# TA_v2.net
KiCad netlist of a schematic drawn in EAGLE
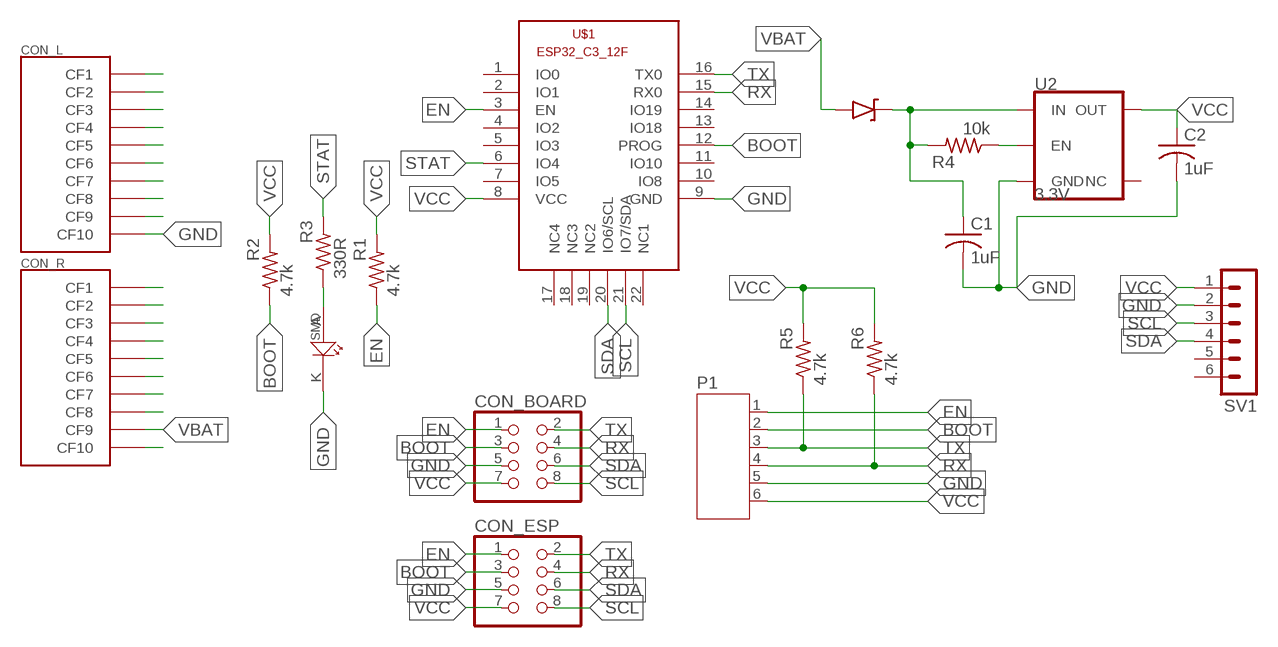
[diagram p0: schematic, sheet 1]

(export (version "E")
  (design (tool "Eeschema 10.0.6"))
  (components
    (comp (ref "C1")
      (value "1uF")
      (footprint "eagle-import:C0805")
      (libsource (lib "eagle-import") (part "C-USC0805"))
    )
    (comp (ref "C2")
      (value "1uF")
      (footprint "eagle-import:C0805")
      (libsource (lib "eagle-import") (part "C-USC0805"))
    )
    (comp (ref "CON_BOARD")
      (value "PINHD-2X4")
      (footprint "eagle-import:2X04")
      (libsource (lib "eagle-import") (part "PINHD-2X4"))
    )
    (comp (ref "CON_ESP")
      (value "PINHD-2X4")
      (footprint "eagle-import:2X04")
      (libsource (lib "eagle-import") (part "PINHD-2X4"))
    )
    (comp (ref "CON_L")
      (value "FEMALE_CON")
      (footprint "eagle-import:FEMALE_HEADER_2")
      (libsource (lib "eagle-import") (part "FEMALE_CON"))
    )
    (comp (ref "CON_R")
      (value "FEMALE_CON")
      (footprint "eagle-import:FEMALE_HEADER_2")
      (libsource (lib "eagle-import") (part "FEMALE_CON"))
    )
    (comp (ref "P1")
      (value "JST-PH6")
      (footprint "eagle-import:JST-PH6")
      (libsource (lib "eagle-import") (part "JST-PH6"))
    )
    (comp (ref "R1")
      (value "4.7k")
      (footprint "eagle-import:R0603")
      (libsource (lib "eagle-import") (part "R-US_R0603"))
    )
    (comp (ref "R2")
      (value "4.7k")
      (footprint "eagle-import:R0603")
      (libsource (lib "eagle-import") (part "R-US_R0603"))
    )
    (comp (ref "R3")
      (value "330R")
      (footprint "eagle-import:R0603")
      (libsource (lib "eagle-import") (part "R-US_R0603"))
    )
    (comp (ref "R4")
      (value "10k")
      (footprint "eagle-import:R0603")
      (libsource (lib "eagle-import") (part "R-US_R0603"))
    )
    (comp (ref "R5")
      (value "4.7k")
      (footprint "eagle-import:R0603")
      (libsource (lib "eagle-import") (part "R-US_R0603"))
    )
    (comp (ref "R6")
      (value "4.7k")
      (footprint "eagle-import:R0603")
      (libsource (lib "eagle-import") (part "R-US_R0603"))
    )
    (comp (ref "SV1")
      (value "MA06-1")
      (footprint "eagle-import:MA06-1")
      (libsource (lib "eagle-import") (part "MA06-1"))
    )
    (comp (ref "U$1")
      (value "ESP32-C3-12FESP32-C3-12F")
      (footprint "eagle-import:ESP32-C3-12F")
      (libsource (lib "eagle-import") (part "ESP32-C3-12FESP32-C3-12F"))
    )
    (comp (ref "U$2")
      (value "1N5819")
      (footprint "eagle-import:SOT-323")
      (libsource (lib "eagle-import") (part "1N5819"))
    )
    (comp (ref "U$3")
      (value "LED_SMD")
      (footprint "eagle-import:LED_0603")
      (libsource (lib "eagle-import") (part "LED_SMD"))
    )
    (comp (ref "U2")
      (value "3.3V")
      (footprint "eagle-import:SOT23-5")
      (libsource (lib "eagle-import") (part "V_REG_AP2112K-3.3V"))
    )
  )
  (nets
    (net (code "1") (name "BOOT") (class "Default")
      (node (ref "CON_BOARD") (pin "3") (pinfunction "3_3") (pintype "passive"))
      (node (ref "CON_ESP") (pin "3") (pinfunction "3_3") (pintype "passive"))
      (node (ref "P1") (pin "2") (pinfunction "2_2") (pintype "passive"))
      (node (ref "R2") (pin "1") (pinfunction "1_1") (pintype "passive"))
      (node (ref "U$1") (pin "12") (pinfunction "PROG_12") (pintype "bidirectional"))
    )
    (net (code "2") (name "EN") (class "Default")
      (node (ref "CON_BOARD") (pin "1") (pinfunction "1_1") (pintype "passive"))
      (node (ref "CON_ESP") (pin "1") (pinfunction "1_1") (pintype "passive"))
      (node (ref "P1") (pin "1") (pinfunction "1_1") (pintype "passive"))
      (node (ref "R1") (pin "1") (pinfunction "1_1") (pintype "passive"))
      (node (ref "U$1") (pin "3") (pinfunction "EN_3") (pintype "bidirectional"))
    )
    (net (code "3") (name "GND") (class "Default")
      (node (ref "C1") (pin "2") (pinfunction "2_2") (pintype "passive"))
      (node (ref "C2") (pin "2") (pinfunction "2_2") (pintype "passive"))
      (node (ref "CON_BOARD") (pin "5") (pinfunction "5_5") (pintype "passive"))
      (node (ref "CON_ESP") (pin "5") (pinfunction "5_5") (pintype "passive"))
      (node (ref "CON_L") (pin "CF10") (pinfunction "CF10_CF10") (pintype "bidirectional"))
      (node (ref "P1") (pin "5") (pinfunction "5_5") (pintype "passive"))
      (node (ref "SV1") (pin "2") (pinfunction "2_2") (pintype "passive"))
      (node (ref "U$1") (pin "9") (pinfunction "GND_9") (pintype "bidirectional"))
      (node (ref "U$3") (pin "K") (pinfunction "K_K") (pintype "bidirectional"))
      (node (ref "U2") (pin "2") (pinfunction "GND_2") (pintype "input"))
    )
    (net (code "4") (name "Net-(R3-Pad1)") (class "Default")
      (node (ref "R3") (pin "1") (pinfunction "1_1") (pintype "passive"))
      (node (ref "U$3") (pin "A") (pinfunction "A_A") (pintype "bidirectional"))
    )
    (net (code "5") (name "Net-(U2-EN)") (class "Default")
      (node (ref "R4") (pin "1") (pinfunction "1_1") (pintype "passive"))
      (node (ref "U2") (pin "3") (pinfunction "EN_3") (pintype "input"))
    )
    (net (code "6") (name "Net-(U2-IN)") (class "Default")
      (node (ref "C1") (pin "1") (pinfunction "1_1") (pintype "passive"))
      (node (ref "R4") (pin "2") (pinfunction "2_2") (pintype "passive"))
      (node (ref "U$2") (pin "K") (pinfunction "K_K") (pintype "bidirectional"))
      (node (ref "U2") (pin "1") (pinfunction "IN_1") (pintype "input"))
    )
    (net (code "7") (name "RX") (class "Default")
      (node (ref "CON_BOARD") (pin "4") (pinfunction "4_4") (pintype "passive"))
      (node (ref "CON_ESP") (pin "4") (pinfunction "4_4") (pintype "passive"))
      (node (ref "P1") (pin "4") (pinfunction "4_4") (pintype "passive"))
      (node (ref "R6") (pin "1") (pinfunction "1_1") (pintype "passive"))
      (node (ref "U$1") (pin "15") (pinfunction "RX0_15") (pintype "bidirectional"))
    )
    (net (code "8") (name "SCL") (class "Default")
      (node (ref "CON_BOARD") (pin "8") (pinfunction "8_8") (pintype "passive"))
      (node (ref "CON_ESP") (pin "8") (pinfunction "8_8") (pintype "passive"))
      (node (ref "SV1") (pin "3") (pinfunction "3_3") (pintype "passive"))
      (node (ref "U$1") (pin "21") (pinfunction "IO7/SDA_21") (pintype "bidirectional"))
    )
    (net (code "9") (name "SDA") (class "Default")
      (node (ref "CON_BOARD") (pin "6") (pinfunction "6_6") (pintype "passive"))
      (node (ref "CON_ESP") (pin "6") (pinfunction "6_6") (pintype "passive"))
      (node (ref "SV1") (pin "4") (pinfunction "4_4") (pintype "passive"))
      (node (ref "U$1") (pin "20") (pinfunction "IO6/SCL_20") (pintype "bidirectional"))
    )
    (net (code "10") (name "STAT") (class "Default")
      (node (ref "R3") (pin "2") (pinfunction "2_2") (pintype "passive"))
      (node (ref "U$1") (pin "6") (pinfunction "IO4_6") (pintype "bidirectional"))
    )
    (net (code "11") (name "TX") (class "Default")
      (node (ref "CON_BOARD") (pin "2") (pinfunction "2_2") (pintype "passive"))
      (node (ref "CON_ESP") (pin "2") (pinfunction "2_2") (pintype "passive"))
      (node (ref "P1") (pin "3") (pinfunction "3_3") (pintype "passive"))
      (node (ref "R5") (pin "1") (pinfunction "1_1") (pintype "passive"))
      (node (ref "U$1") (pin "16") (pinfunction "TX0_16") (pintype "bidirectional"))
    )
    (net (code "12") (name "VBAT") (class "Default")
      (node (ref "CON_R") (pin "CF9") (pinfunction "CF9_CF9") (pintype "bidirectional"))
      (node (ref "U$2") (pin "A") (pinfunction "A_A") (pintype "bidirectional"))
    )
    (net (code "13") (name "VCC") (class "Default")
      (node (ref "C2") (pin "1") (pinfunction "1_1") (pintype "passive"))
      (node (ref "CON_BOARD") (pin "7") (pinfunction "7_7") (pintype "passive"))
      (node (ref "CON_ESP") (pin "7") (pinfunction "7_7") (pintype "passive"))
      (node (ref "P1") (pin "6") (pinfunction "6_6") (pintype "passive"))
      (node (ref "R1") (pin "2") (pinfunction "2_2") (pintype "passive"))
      (node (ref "R2") (pin "2") (pinfunction "2_2") (pintype "passive"))
      (node (ref "R5") (pin "2") (pinfunction "2_2") (pintype "passive"))
      (node (ref "R6") (pin "2") (pinfunction "2_2") (pintype "passive"))
      (node (ref "SV1") (pin "1") (pinfunction "1_1") (pintype "passive"))
      (node (ref "U$1") (pin "8") (pinfunction "VCC_8") (pintype "bidirectional"))
      (node (ref "U2") (pin "5") (pinfunction "OUT_5") (pintype "passive"))
    )
    (net (code "14") (name "unconnected-(CON_L-PadCF1)") (class "Default")
      (node (ref "CON_L") (pin "CF1") (pinfunction "CF1_CF1") (pintype "bidirectional"))
    )
    (net (code "15") (name "unconnected-(CON_L-PadCF2)") (class "Default")
      (node (ref "CON_L") (pin "CF2") (pinfunction "CF2_CF2") (pintype "bidirectional"))
    )
    (net (code "16") (name "unconnected-(CON_L-PadCF3)") (class "Default")
      (node (ref "CON_L") (pin "CF3") (pinfunction "CF3_CF3") (pintype "bidirectional"))
    )
    (net (code "17") (name "unconnected-(CON_L-PadCF4)") (class "Default")
      (node (ref "CON_L") (pin "CF4") (pinfunction "CF4_CF4") (pintype "bidirectional"))
    )
    (net (code "18") (name "unconnected-(CON_L-PadCF5)") (class "Default")
      (node (ref "CON_L") (pin "CF5") (pinfunction "CF5_CF5") (pintype "bidirectional"))
    )
    (net (code "19") (name "unconnected-(CON_L-PadCF6)") (class "Default")
      (node (ref "CON_L") (pin "CF6") (pinfunction "CF6_CF6") (pintype "bidirectional"))
    )
    (net (code "20") (name "unconnected-(CON_L-PadCF7)") (class "Default")
      (node (ref "CON_L") (pin "CF7") (pinfunction "CF7_CF7") (pintype "bidirectional"))
    )
    (net (code "21") (name "unconnected-(CON_L-PadCF8)") (class "Default")
      (node (ref "CON_L") (pin "CF8") (pinfunction "CF8_CF8") (pintype "bidirectional"))
    )
    (net (code "22") (name "unconnected-(CON_L-PadCF9)") (class "Default")
      (node (ref "CON_L") (pin "CF9") (pinfunction "CF9_CF9") (pintype "bidirectional"))
    )
    (net (code "23") (name "unconnected-(CON_R-PadCF1)") (class "Default")
      (node (ref "CON_R") (pin "CF1") (pinfunction "CF1_CF1") (pintype "bidirectional"))
    )
    (net (code "24") (name "unconnected-(CON_R-PadCF2)") (class "Default")
      (node (ref "CON_R") (pin "CF2") (pinfunction "CF2_CF2") (pintype "bidirectional"))
    )
    (net (code "25") (name "unconnected-(CON_R-PadCF3)") (class "Default")
      (node (ref "CON_R") (pin "CF3") (pinfunction "CF3_CF3") (pintype "bidirectional"))
    )
    (net (code "26") (name "unconnected-(CON_R-PadCF4)") (class "Default")
      (node (ref "CON_R") (pin "CF4") (pinfunction "CF4_CF4") (pintype "bidirectional"))
    )
    (net (code "27") (name "unconnected-(CON_R-PadCF5)") (class "Default")
      (node (ref "CON_R") (pin "CF5") (pinfunction "CF5_CF5") (pintype "bidirectional"))
    )
    (net (code "28") (name "unconnected-(CON_R-PadCF6)") (class "Default")
      (node (ref "CON_R") (pin "CF6") (pinfunction "CF6_CF6") (pintype "bidirectional"))
    )
    (net (code "29") (name "unconnected-(CON_R-PadCF7)") (class "Default")
      (node (ref "CON_R") (pin "CF7") (pinfunction "CF7_CF7") (pintype "bidirectional"))
    )
    (net (code "30") (name "unconnected-(CON_R-PadCF8)") (class "Default")
      (node (ref "CON_R") (pin "CF8") (pinfunction "CF8_CF8") (pintype "bidirectional"))
    )
    (net (code "31") (name "unconnected-(CON_R-PadCF10)") (class "Default")
      (node (ref "CON_R") (pin "CF10") (pinfunction "CF10_CF10") (pintype "bidirectional"))
    )
    (net (code "32") (name "unconnected-(SV1-Pad5)") (class "Default")
      (node (ref "SV1") (pin "5") (pinfunction "5_5") (pintype "passive"))
    )
    (net (code "33") (name "unconnected-(SV1-Pad6)") (class "Default")
      (node (ref "SV1") (pin "6") (pinfunction "6_6") (pintype "passive"))
    )
    (net (code "34") (name "unconnected-(U$1-IO0-Pad1)") (class "Default")
      (node (ref "U$1") (pin "1") (pinfunction "IO0_1") (pintype "bidirectional"))
    )
    (net (code "35") (name "unconnected-(U$1-IO1-Pad2)") (class "Default")
      (node (ref "U$1") (pin "2") (pinfunction "IO1_2") (pintype "bidirectional"))
    )
    (net (code "36") (name "unconnected-(U$1-IO2-Pad4)") (class "Default")
      (node (ref "U$1") (pin "4") (pinfunction "IO2_4") (pintype "bidirectional"))
    )
    (net (code "37") (name "unconnected-(U$1-IO3-Pad5)") (class "Default")
      (node (ref "U$1") (pin "5") (pinfunction "IO3_5") (pintype "bidirectional"))
    )
    (net (code "38") (name "unconnected-(U$1-IO5-Pad7)") (class "Default")
      (node (ref "U$1") (pin "7") (pinfunction "IO5_7") (pintype "bidirectional"))
    )
    (net (code "39") (name "unconnected-(U$1-IO8-Pad10)") (class "Default")
      (node (ref "U$1") (pin "10") (pinfunction "IO8_10") (pintype "bidirectional"))
    )
    (net (code "40") (name "unconnected-(U$1-IO10-Pad11)") (class "Default")
      (node (ref "U$1") (pin "11") (pinfunction "IO10_11") (pintype "bidirectional"))
    )
    (net (code "41") (name "unconnected-(U$1-IO18-Pad13)") (class "Default")
      (node (ref "U$1") (pin "13") (pinfunction "IO18_13") (pintype "bidirectional"))
    )
    (net (code "42") (name "unconnected-(U$1-IO19-Pad14)") (class "Default")
      (node (ref "U$1") (pin "14") (pinfunction "IO19_14") (pintype "bidirectional"))
    )
    (net (code "43") (name "unconnected-(U$1-NC1-Pad22)") (class "Default")
      (node (ref "U$1") (pin "22") (pinfunction "NC1_22") (pintype "bidirectional"))
    )
    (net (code "44") (name "unconnected-(U$1-NC2-Pad19)") (class "Default")
      (node (ref "U$1") (pin "19") (pinfunction "NC2_19") (pintype "bidirectional"))
    )
    (net (code "45") (name "unconnected-(U$1-NC3-Pad18)") (class "Default")
      (node (ref "U$1") (pin "18") (pinfunction "NC3_18") (pintype "bidirectional"))
    )
    (net (code "46") (name "unconnected-(U$1-NC4-Pad17)") (class "Default")
      (node (ref "U$1") (pin "17") (pinfunction "NC4_17") (pintype "bidirectional"))
    )
    (net (code "47") (name "unconnected-(U2-NC-Pad4)") (class "Default")
      (node (ref "U2") (pin "4") (pinfunction "NC_4") (pintype "no_connect"))
    )
  )
)
